# MCU.net
KiCad netlist of a schematic drawn in Altium Designer
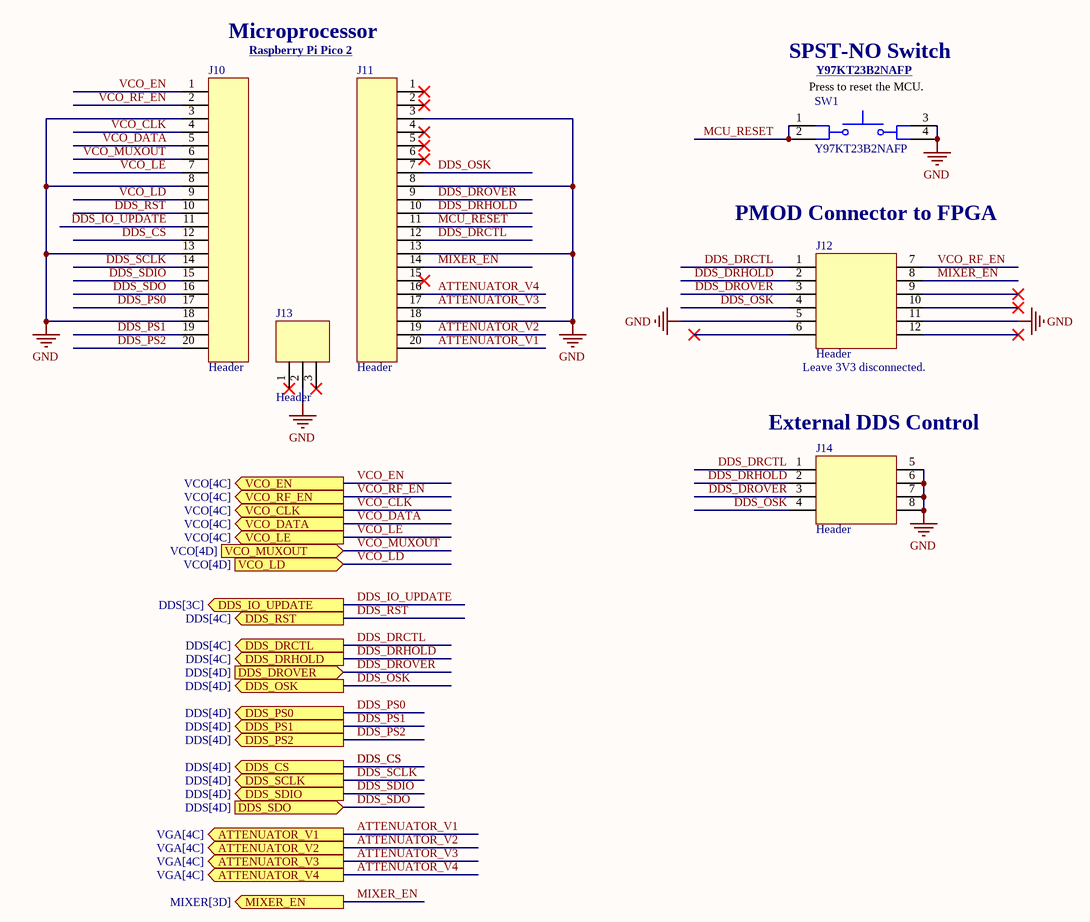
[diagram p0: MCU.SchDoc]

(export (version "E")
  (design (tool "Eeschema 10.0.6"))
  (components
    (comp (ref "J10")
      (value "Header")
      (footprint "CONN_1x20_2.54mm_PinSocket_Vertical")
      (description "WR-PHD 2.54 mm Socket Header; 20 pins")
      (fields
        (field (name "MANUFACTURER") "Wurth Elektronik")
        (field (name "MANUFACTURER PART NUMBER") "61302011821")
      )
      (libsource (lib "") (part "CONN_1x20_2.54mm_PinSocket_Vertical_1"))
    )
    (comp (ref "J11")
      (value "Header")
      (footprint "CONN_1x20_2.54mm_PinSocket_Vertical")
      (description "WR-PHD 2.54 mm Socket Header; 20 pins")
      (fields
        (field (name "MANUFACTURER") "Wurth Elektronik")
        (field (name "MANUFACTURER PART NUMBER") "61302011821")
      )
      (libsource (lib "Titan") (part "CONN_1x20_2.54mm_PinSocket_Vertical"))
    )
    (comp (ref "J12")
      (value "Header")
      (footprint "CONN_2x6_2.54mm_PinHeader_Horizontal")
      (description "Conn Unshrouded Header HDR 12 POS 2.54mm Solder RA Top Entry Thru-Hole Bag")
      (fields
        (field (name "MANUFACTURER") "Adam Tech")
        (field (name "MANUFACTURER PART NUMBER") "PH2RA-12-UA")
      )
      (libsource (lib "Titan") (part "CONN_2x6_2.54mm_PinHeader_Horizontal"))
    )
    (comp (ref "J13")
      (value "Header")
      (footprint "CONN_1x3_2.54mm_PinSocket_Vertical")
      (description "Connector Header Through Hole 3 position 0.100\" (2.54mm)-FAN Control Connector")
      (fields
        (field (name "MANUFACTURER") "Wurth Elektronik")
        (field (name "MANUFACTURER PART NUMBER") "61300311821")
      )
      (libsource (lib "Titan") (part "CONN_1x3_2.54mm_PinSocket_Vertical"))
    )
    (comp (ref "J14")
      (value "Header")
      (footprint "CONN_2x4_2.54mm_PinHeader_Vertical")
      (description "Pin Header, Board-to-Board, 2.54 mm, 2 Rows, 8 Contacts, Through Hole, TSW Series")
      (fields
        (field (name "MANUFACTURER") "Samtec")
        (field (name "MANUFACTURER PART NUMBER") "TSW-104-07-F-D")
      )
      (libsource (lib "Titan") (part "CONN_2x4_2.54mm_PinHeader_Vertical"))
    )
    (comp (ref "SW1")
      (value "Y97KT23B2NAFP")
      (footprint "PTS647")
      (description "Switch Tactile OFF Mom SPST Round Button Gull Wing 50mA 12VDC 100000Cycles 1.77N Surface Mount T/R")
      (fields (field (name "MANUFACTURER") "C&K"))
      (libsource (lib "Titan") (part "Y97KT23B2NAFP"))
    )
  )
  (nets
    (net (code "1") (name "/ATTENUATOR_V1") (class "Default")
      (node (ref "J11") (pin "20") (pintype "passive"))
    )
    (net (code "2") (name "/ATTENUATOR_V2") (class "Default")
      (node (ref "J11") (pin "19") (pintype "passive"))
    )
    (net (code "3") (name "/ATTENUATOR_V3") (class "Default")
      (node (ref "J11") (pin "17") (pintype "passive"))
    )
    (net (code "4") (name "/ATTENUATOR_V4") (class "Default")
      (node (ref "J11") (pin "16") (pintype "passive"))
    )
    (net (code "5") (name "/DDS_CS") (class "Default") (node (ref "J10") (pin "12") (pintype "passive")))
    (net (code "6") (name "/DDS_DRCTL") (class "Default")
      (node (ref "J11") (pin "12") (pintype "passive"))
      (node (ref "J12") (pin "1") (pintype "passive"))
      (node (ref "J14") (pin "1") (pintype "passive"))
    )
    (net (code "7") (name "/DDS_DRHOLD") (class "Default")
      (node (ref "J11") (pin "10") (pintype "passive"))
      (node (ref "J12") (pin "2") (pintype "passive"))
      (node (ref "J14") (pin "2") (pintype "passive"))
    )
    (net (code "8") (name "/DDS_DROVER") (class "Default")
      (node (ref "J11") (pin "9") (pintype "passive"))
      (node (ref "J12") (pin "3") (pintype "passive"))
      (node (ref "J14") (pin "3") (pintype "passive"))
    )
    (net (code "9") (name "/DDS_IO_UPDATE") (class "Default")
      (node (ref "J10") (pin "11") (pintype "passive"))
    )
    (net (code "10") (name "/DDS_OSK") (class "Default")
      (node (ref "J11") (pin "7") (pintype "passive"))
      (node (ref "J12") (pin "4") (pintype "passive"))
      (node (ref "J14") (pin "4") (pintype "passive"))
    )
    (net (code "11") (name "/DDS_PS0") (class "Default") (node (ref "J10") (pin "17") (pintype "passive")))
    (net (code "12") (name "/DDS_PS1") (class "Default") (node (ref "J10") (pin "19") (pintype "passive")))
    (net (code "13") (name "/DDS_PS2") (class "Default") (node (ref "J10") (pin "20") (pintype "passive")))
    (net (code "14") (name "/DDS_RST") (class "Default") (node (ref "J10") (pin "10") (pintype "passive")))
    (net (code "15") (name "/DDS_SCLK") (class "Default") (node (ref "J10") (pin "14") (pintype "passive")))
    (net (code "16") (name "/DDS_SDIO") (class "Default") (node (ref "J10") (pin "15") (pintype "passive")))
    (net (code "17") (name "/DDS_SDO") (class "Default") (node (ref "J10") (pin "16") (pintype "passive")))
    (net (code "18") (name "/MCU_RESET") (class "Default")
      (node (ref "J11") (pin "11") (pintype "passive"))
      (node (ref "SW1") (pin "1") (pintype "passive"))
      (node (ref "SW1") (pin "2") (pintype "passive"))
    )
    (net (code "19") (name "/MIXER_EN") (class "Default")
      (node (ref "J11") (pin "14") (pintype "passive"))
      (node (ref "J12") (pin "8") (pintype "passive"))
    )
    (net (code "20") (name "/VCO_CLK") (class "Default") (node (ref "J10") (pin "4") (pintype "passive")))
    (net (code "21") (name "/VCO_DATA") (class "Default") (node (ref "J10") (pin "5") (pintype "passive")))
    (net (code "22") (name "/VCO_EN") (class "Default") (node (ref "J10") (pin "1") (pintype "passive")))
    (net (code "23") (name "/VCO_LD") (class "Default") (node (ref "J10") (pin "9") (pintype "passive")))
    (net (code "24") (name "/VCO_LE") (class "Default") (node (ref "J10") (pin "7") (pintype "passive")))
    (net (code "25") (name "/VCO_MUXOUT") (class "Default") (node (ref "J10") (pin "6") (pintype "passive")))
    (net (code "26") (name "/VCO_RF_EN") (class "Default")
      (node (ref "J10") (pin "2") (pintype "passive"))
      (node (ref "J12") (pin "7") (pintype "passive"))
    )
    (net (code "27") (name "GND") (class "Default")
      (node (ref "J10") (pin "13") (pintype "passive"))
      (node (ref "J10") (pin "18") (pintype "passive"))
      (node (ref "J10") (pin "3") (pintype "passive"))
      (node (ref "J10") (pin "8") (pintype "passive"))
      (node (ref "J11") (pin "13") (pintype "passive"))
      (node (ref "J11") (pin "18") (pintype "passive"))
      (node (ref "J11") (pin "3") (pintype "passive"))
      (node (ref "J11") (pin "8") (pintype "passive"))
      (node (ref "J12") (pin "11") (pintype "passive"))
      (node (ref "J12") (pin "5") (pintype "passive"))
      (node (ref "J13") (pin "2") (pintype "passive"))
      (node (ref "J14") (pin "5") (pintype "passive"))
      (node (ref "J14") (pin "6") (pintype "passive"))
      (node (ref "J14") (pin "7") (pintype "passive"))
      (node (ref "J14") (pin "8") (pintype "passive"))
      (node (ref "SW1") (pin "3") (pintype "passive"))
      (node (ref "SW1") (pin "4") (pintype "passive"))
    )
    (net (code "28") (name "unconnected-(J11-Pad1)") (class "Default")
      (node (ref "J11") (pin "1") (pintype "passive+no_connect"))
    )
    (net (code "29") (name "unconnected-(J11-Pad2)") (class "Default")
      (node (ref "J11") (pin "2") (pintype "passive+no_connect"))
    )
    (net (code "30") (name "unconnected-(J11-Pad4)") (class "Default")
      (node (ref "J11") (pin "4") (pintype "passive+no_connect"))
    )
    (net (code "31") (name "unconnected-(J11-Pad5)") (class "Default")
      (node (ref "J11") (pin "5") (pintype "passive+no_connect"))
    )
    (net (code "32") (name "unconnected-(J11-Pad6)") (class "Default")
      (node (ref "J11") (pin "6") (pintype "passive+no_connect"))
    )
    (net (code "33") (name "unconnected-(J11-Pad15)") (class "Default")
      (node (ref "J11") (pin "15") (pintype "passive+no_connect"))
    )
    (net (code "34") (name "unconnected-(J12-Pad6)") (class "Default")
      (node (ref "J12") (pin "6") (pintype "passive+no_connect"))
    )
    (net (code "35") (name "unconnected-(J12-Pad9)") (class "Default")
      (node (ref "J12") (pin "9") (pintype "passive+no_connect"))
    )
    (net (code "36") (name "unconnected-(J12-Pad10)") (class "Default")
      (node (ref "J12") (pin "10") (pintype "passive+no_connect"))
    )
    (net (code "37") (name "unconnected-(J12-Pad12)") (class "Default")
      (node (ref "J12") (pin "12") (pintype "passive+no_connect"))
    )
    (net (code "38") (name "unconnected-(J13-Pad1)") (class "Default")
      (node (ref "J13") (pin "1") (pintype "passive+no_connect"))
    )
    (net (code "39") (name "unconnected-(J13-Pad3)") (class "Default")
      (node (ref "J13") (pin "3") (pintype "passive+no_connect"))
    )
  )
)
